# SCH_Naginata-left_2026-06-09.net
KiCad netlist of a schematic drawn in EasyEDA
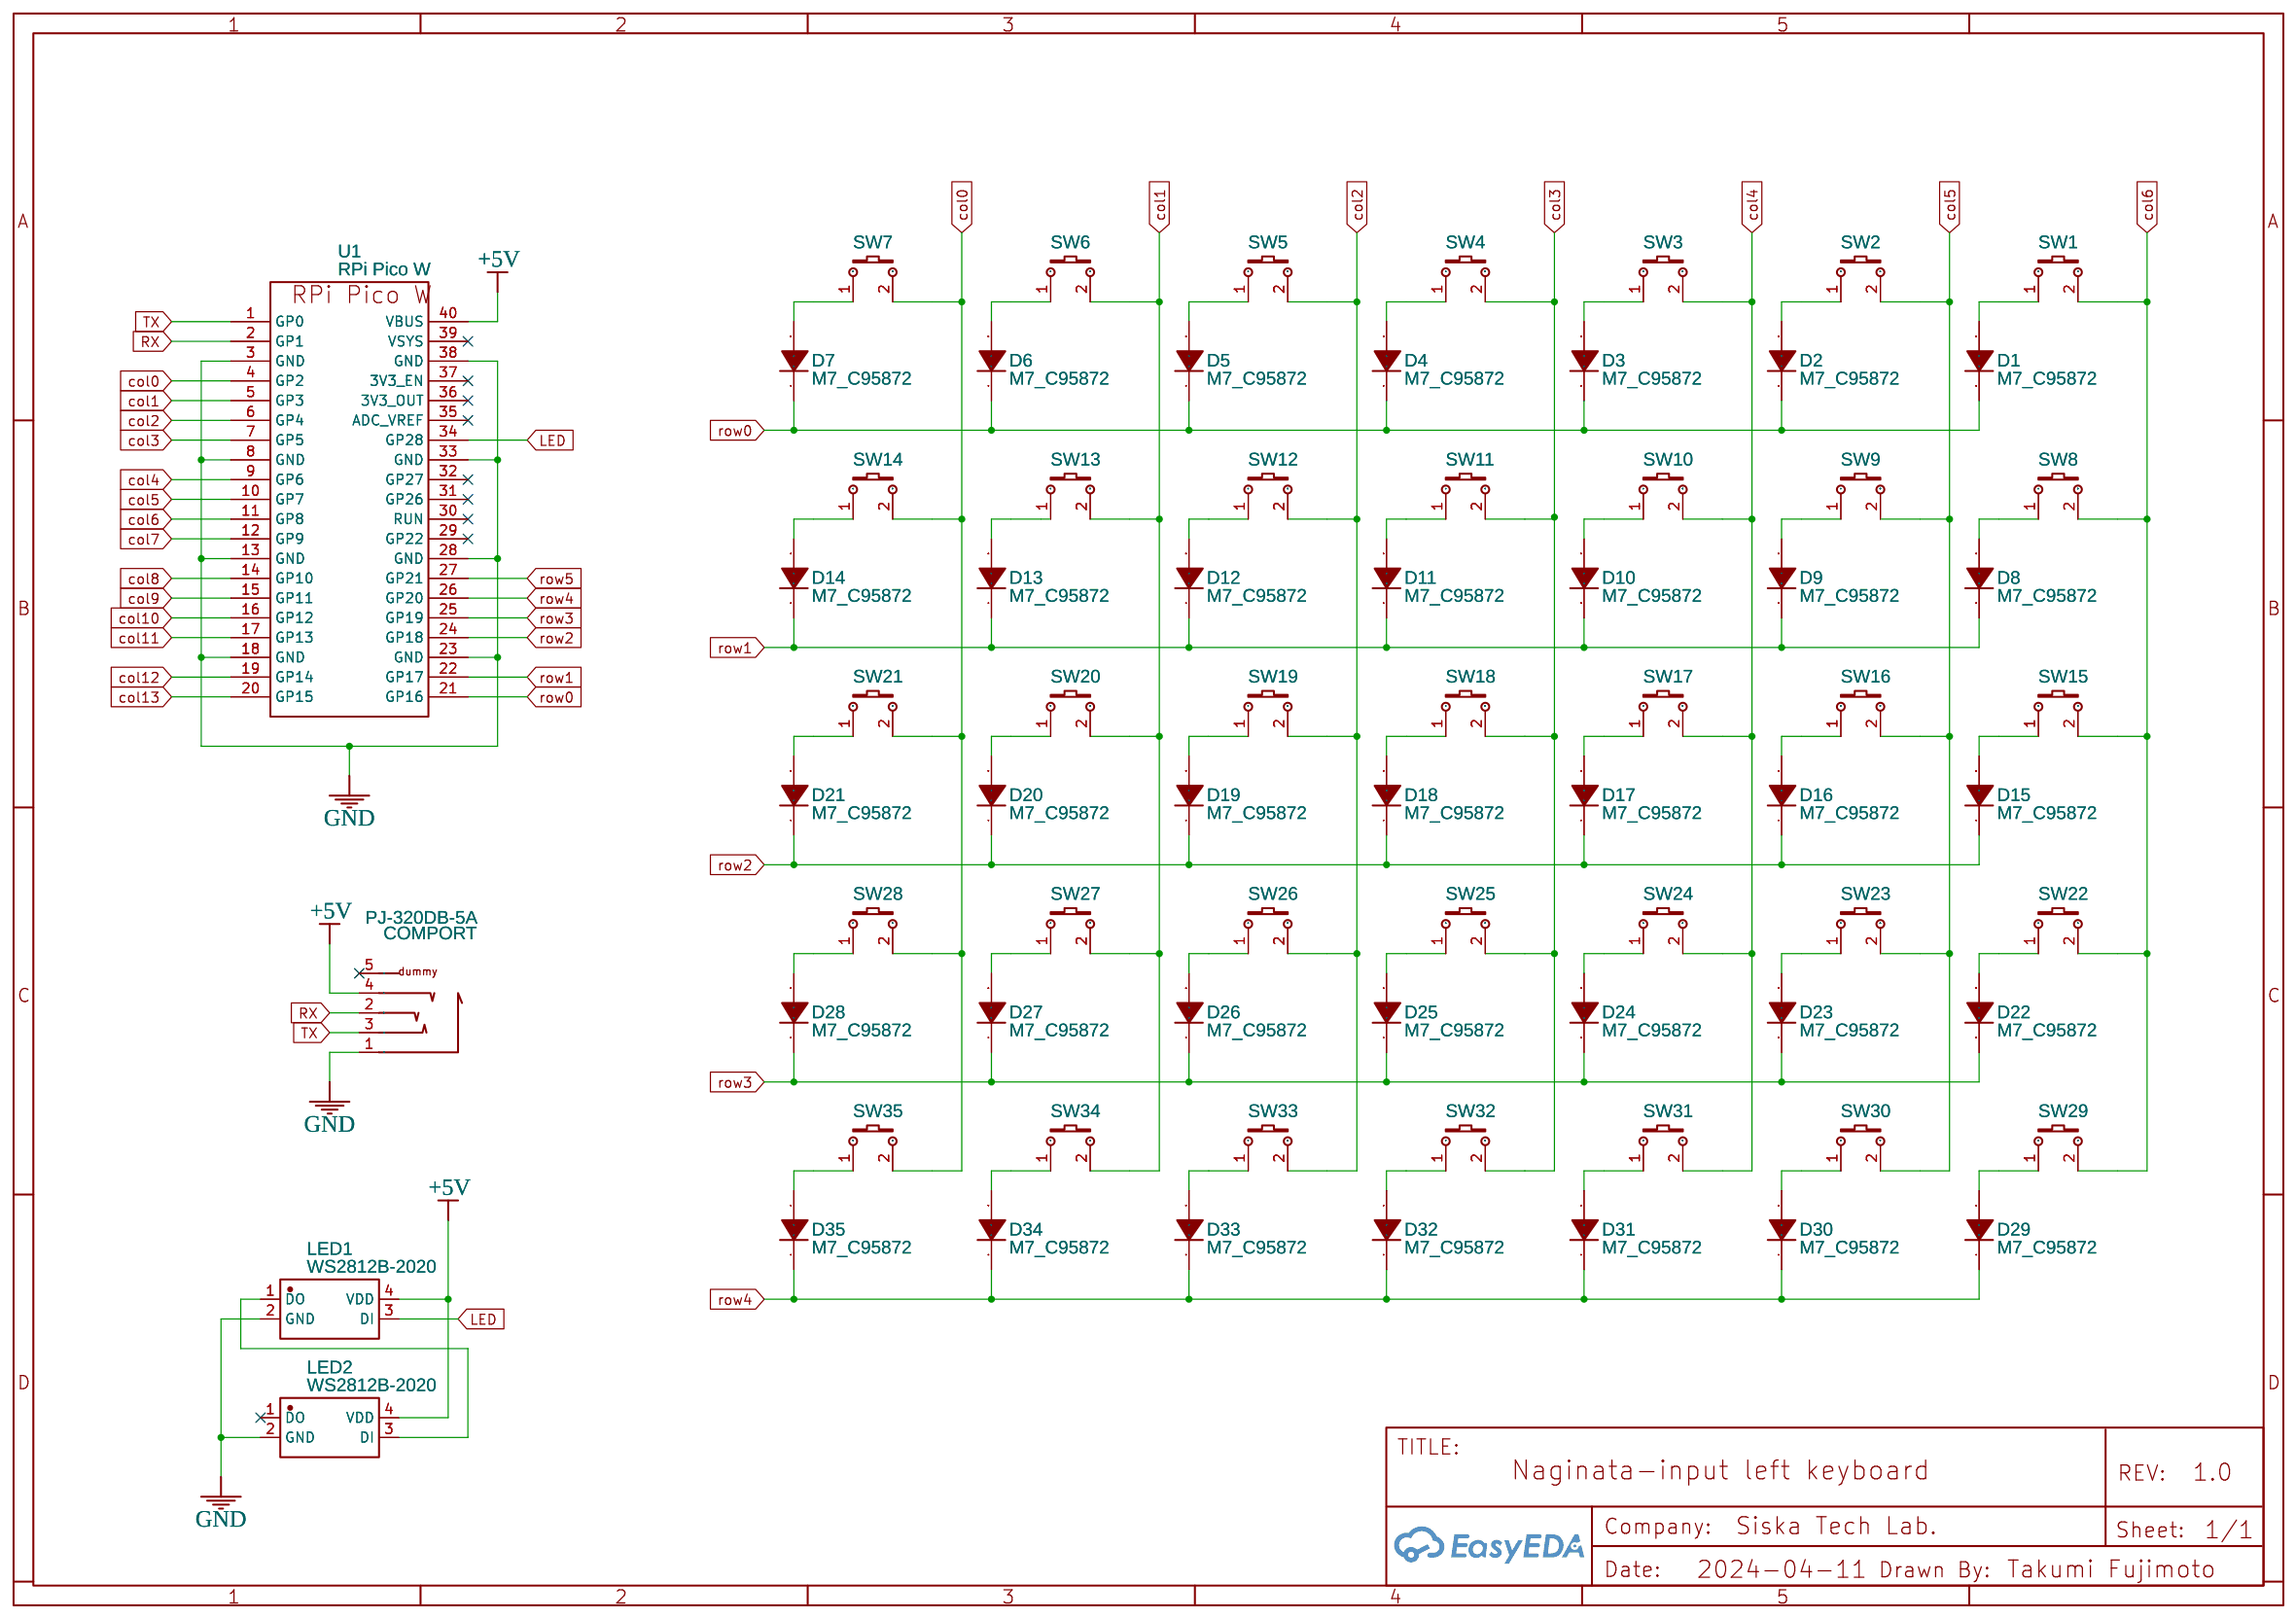
[diagram p0: schematic sheet]

(export (version "E")
  (design (tool "Eeschema 10.0.6"))
  (components
    (comp (ref "COMPORT")
      (value "PJ-320DB-5A")
      (fields (field (name "Manufacturer") "韩国韩荣"))
      (libsource (lib "") (part "PJ-320DB-5A"))
    )
    (comp (ref "D1")
      (value "M7_C95872")
      (fields (field (name "Manufacturer Part") "M7") (field (name "Manufacturer") "MDD"))
      (libsource (lib "") (part "M7_C95872"))
    )
    (comp (ref "D2")
      (value "M7_C95872")
      (fields (field (name "Manufacturer Part") "M7") (field (name "Manufacturer") "MDD"))
      (libsource (lib "") (part "M7_C95872"))
    )
    (comp (ref "D3")
      (value "M7_C95872")
      (fields (field (name "Manufacturer Part") "M7") (field (name "Manufacturer") "MDD"))
      (libsource (lib "") (part "M7_C95872"))
    )
    (comp (ref "D4")
      (value "M7_C95872")
      (fields (field (name "Manufacturer Part") "M7") (field (name "Manufacturer") "MDD"))
      (libsource (lib "") (part "M7_C95872"))
    )
    (comp (ref "D5")
      (value "M7_C95872")
      (fields (field (name "Manufacturer Part") "M7") (field (name "Manufacturer") "MDD"))
      (libsource (lib "") (part "M7_C95872"))
    )
    (comp (ref "D6")
      (value "M7_C95872")
      (fields (field (name "Manufacturer Part") "M7") (field (name "Manufacturer") "MDD"))
      (libsource (lib "") (part "M7_C95872"))
    )
    (comp (ref "D7")
      (value "M7_C95872")
      (fields (field (name "Manufacturer Part") "M7") (field (name "Manufacturer") "MDD"))
      (libsource (lib "") (part "M7_C95872"))
    )
    (comp (ref "D8")
      (value "M7_C95872")
      (fields (field (name "Manufacturer Part") "M7") (field (name "Manufacturer") "MDD"))
      (libsource (lib "") (part "M7_C95872"))
    )
    (comp (ref "D9")
      (value "M7_C95872")
      (fields (field (name "Manufacturer Part") "M7") (field (name "Manufacturer") "MDD"))
      (libsource (lib "") (part "M7_C95872"))
    )
    (comp (ref "D10")
      (value "M7_C95872")
      (fields (field (name "Manufacturer Part") "M7") (field (name "Manufacturer") "MDD"))
      (libsource (lib "") (part "M7_C95872"))
    )
    (comp (ref "D11")
      (value "M7_C95872")
      (fields (field (name "Manufacturer Part") "M7") (field (name "Manufacturer") "MDD"))
      (libsource (lib "") (part "M7_C95872"))
    )
    (comp (ref "D12")
      (value "M7_C95872")
      (fields (field (name "Manufacturer Part") "M7") (field (name "Manufacturer") "MDD"))
      (libsource (lib "") (part "M7_C95872"))
    )
    (comp (ref "D13")
      (value "M7_C95872")
      (fields (field (name "Manufacturer Part") "M7") (field (name "Manufacturer") "MDD"))
      (libsource (lib "") (part "M7_C95872"))
    )
    (comp (ref "D14")
      (value "M7_C95872")
      (fields (field (name "Manufacturer Part") "M7") (field (name "Manufacturer") "MDD"))
      (libsource (lib "") (part "M7_C95872"))
    )
    (comp (ref "D15")
      (value "M7_C95872")
      (fields (field (name "Manufacturer Part") "M7") (field (name "Manufacturer") "MDD"))
      (libsource (lib "") (part "M7_C95872"))
    )
    (comp (ref "D16")
      (value "M7_C95872")
      (fields (field (name "Manufacturer Part") "M7") (field (name "Manufacturer") "MDD"))
      (libsource (lib "") (part "M7_C95872"))
    )
    (comp (ref "D17")
      (value "M7_C95872")
      (fields (field (name "Manufacturer Part") "M7") (field (name "Manufacturer") "MDD"))
      (libsource (lib "") (part "M7_C95872"))
    )
    (comp (ref "D18")
      (value "M7_C95872")
      (fields (field (name "Manufacturer Part") "M7") (field (name "Manufacturer") "MDD"))
      (libsource (lib "") (part "M7_C95872"))
    )
    (comp (ref "D19")
      (value "M7_C95872")
      (fields (field (name "Manufacturer Part") "M7") (field (name "Manufacturer") "MDD"))
      (libsource (lib "") (part "M7_C95872"))
    )
    (comp (ref "D20")
      (value "M7_C95872")
      (fields (field (name "Manufacturer Part") "M7") (field (name "Manufacturer") "MDD"))
      (libsource (lib "") (part "M7_C95872"))
    )
    (comp (ref "D21")
      (value "M7_C95872")
      (fields (field (name "Manufacturer Part") "M7") (field (name "Manufacturer") "MDD"))
      (libsource (lib "") (part "M7_C95872"))
    )
    (comp (ref "D22")
      (value "M7_C95872")
      (fields (field (name "Manufacturer Part") "M7") (field (name "Manufacturer") "MDD"))
      (libsource (lib "") (part "M7_C95872"))
    )
    (comp (ref "D23")
      (value "M7_C95872")
      (fields (field (name "Manufacturer Part") "M7") (field (name "Manufacturer") "MDD"))
      (libsource (lib "") (part "M7_C95872"))
    )
    (comp (ref "D24")
      (value "M7_C95872")
      (fields (field (name "Manufacturer Part") "M7") (field (name "Manufacturer") "MDD"))
      (libsource (lib "") (part "M7_C95872"))
    )
    (comp (ref "D25")
      (value "M7_C95872")
      (fields (field (name "Manufacturer Part") "M7") (field (name "Manufacturer") "MDD"))
      (libsource (lib "") (part "M7_C95872"))
    )
    (comp (ref "D26")
      (value "M7_C95872")
      (fields (field (name "Manufacturer Part") "M7") (field (name "Manufacturer") "MDD"))
      (libsource (lib "") (part "M7_C95872"))
    )
    (comp (ref "D27")
      (value "M7_C95872")
      (fields (field (name "Manufacturer Part") "M7") (field (name "Manufacturer") "MDD"))
      (libsource (lib "") (part "M7_C95872"))
    )
    (comp (ref "D28")
      (value "M7_C95872")
      (fields (field (name "Manufacturer Part") "M7") (field (name "Manufacturer") "MDD"))
      (libsource (lib "") (part "M7_C95872"))
    )
    (comp (ref "D29")
      (value "M7_C95872")
      (fields (field (name "Manufacturer Part") "M7") (field (name "Manufacturer") "MDD"))
      (libsource (lib "") (part "M7_C95872"))
    )
    (comp (ref "D30")
      (value "M7_C95872")
      (fields (field (name "Manufacturer Part") "M7") (field (name "Manufacturer") "MDD"))
      (libsource (lib "") (part "M7_C95872"))
    )
    (comp (ref "D31")
      (value "M7_C95872")
      (fields (field (name "Manufacturer Part") "M7") (field (name "Manufacturer") "MDD"))
      (libsource (lib "") (part "M7_C95872"))
    )
    (comp (ref "D32")
      (value "M7_C95872")
      (fields (field (name "Manufacturer Part") "M7") (field (name "Manufacturer") "MDD"))
      (libsource (lib "") (part "M7_C95872"))
    )
    (comp (ref "D33")
      (value "M7_C95872")
      (fields (field (name "Manufacturer Part") "M7") (field (name "Manufacturer") "MDD"))
      (libsource (lib "") (part "M7_C95872"))
    )
    (comp (ref "D34")
      (value "M7_C95872")
      (fields (field (name "Manufacturer Part") "M7") (field (name "Manufacturer") "MDD"))
      (libsource (lib "") (part "M7_C95872"))
    )
    (comp (ref "D35")
      (value "M7_C95872")
      (fields (field (name "Manufacturer Part") "M7") (field (name "Manufacturer") "MDD"))
      (libsource (lib "") (part "M7_C95872"))
    )
    (comp (ref "LED1")
      (value "WS2812B-2020")
      (fields (field (name "Manufacturer") "worldsemi"))
      (libsource (lib "") (part "WS2812B-2020"))
    )
    (comp (ref "LED2")
      (value "WS2812B-2020")
      (fields (field (name "Manufacturer") "worldsemi"))
      (libsource (lib "") (part "WS2812B-2020"))
    )
    (comp (ref "SW1")
      (value "MX1A-11NW")
      (fields (field (name "Manufacturer") "CHERRY"))
      (libsource (lib "") (part "MX1A-11NW"))
    )
    (comp (ref "SW2")
      (value "MX1A-11NW")
      (fields (field (name "Manufacturer") "CHERRY"))
      (libsource (lib "") (part "MX1A-11NW"))
    )
    (comp (ref "SW3")
      (value "MX1A-11NW")
      (fields (field (name "Manufacturer") "CHERRY"))
      (libsource (lib "") (part "MX1A-11NW"))
    )
    (comp (ref "SW4")
      (value "MX1A-11NW")
      (fields (field (name "Manufacturer") "CHERRY"))
      (libsource (lib "") (part "MX1A-11NW"))
    )
    (comp (ref "SW5")
      (value "MX1A-11NW")
      (fields (field (name "Manufacturer") "CHERRY"))
      (libsource (lib "") (part "MX1A-11NW"))
    )
    (comp (ref "SW6")
      (value "MX1A-11NW")
      (fields (field (name "Manufacturer") "CHERRY"))
      (libsource (lib "") (part "MX1A-11NW"))
    )
    (comp (ref "SW7")
      (value "MX1A-11NW")
      (fields (field (name "Manufacturer") "CHERRY"))
      (libsource (lib "") (part "MX1A-11NW"))
    )
    (comp (ref "SW8")
      (value "MX1A-11NW")
      (fields (field (name "Manufacturer") "CHERRY"))
      (libsource (lib "") (part "MX1A-11NW"))
    )
    (comp (ref "SW9")
      (value "MX1A-11NW")
      (fields (field (name "Manufacturer") "CHERRY"))
      (libsource (lib "") (part "MX1A-11NW"))
    )
    (comp (ref "SW10")
      (value "MX1A-11NW")
      (fields (field (name "Manufacturer") "CHERRY"))
      (libsource (lib "") (part "MX1A-11NW"))
    )
    (comp (ref "SW11")
      (value "MX1A-11NW")
      (fields (field (name "Manufacturer") "CHERRY"))
      (libsource (lib "") (part "MX1A-11NW"))
    )
    (comp (ref "SW12")
      (value "MX1A-11NW")
      (fields (field (name "Manufacturer") "CHERRY"))
      (libsource (lib "") (part "MX1A-11NW"))
    )
    (comp (ref "SW13")
      (value "MX1A-11NW")
      (fields (field (name "Manufacturer") "CHERRY"))
      (libsource (lib "") (part "MX1A-11NW"))
    )
    (comp (ref "SW14")
      (value "MX1A-11NW")
      (fields (field (name "Manufacturer") "CHERRY"))
      (libsource (lib "") (part "MX1A-11NW"))
    )
    (comp (ref "SW15")
      (value "MX1A-11NW")
      (fields (field (name "Manufacturer") "CHERRY"))
      (libsource (lib "") (part "MX1A-11NW"))
    )
    (comp (ref "SW16")
      (value "MX1A-11NW")
      (fields (field (name "Manufacturer") "CHERRY"))
      (libsource (lib "") (part "MX1A-11NW"))
    )
    (comp (ref "SW17")
      (value "MX1A-11NW")
      (fields (field (name "Manufacturer") "CHERRY"))
      (libsource (lib "") (part "MX1A-11NW"))
    )
    (comp (ref "SW18")
      (value "MX1A-11NW")
      (fields (field (name "Manufacturer") "CHERRY"))
      (libsource (lib "") (part "MX1A-11NW"))
    )
    (comp (ref "SW19")
      (value "MX1A-11NW")
      (fields (field (name "Manufacturer") "CHERRY"))
      (libsource (lib "") (part "MX1A-11NW"))
    )
    (comp (ref "SW20")
      (value "MX1A-11NW")
      (fields (field (name "Manufacturer") "CHERRY"))
      (libsource (lib "") (part "MX1A-11NW"))
    )
    (comp (ref "SW21")
      (value "MX1A-11NW")
      (fields (field (name "Manufacturer") "CHERRY"))
      (libsource (lib "") (part "MX1A-11NW"))
    )
    (comp (ref "SW22")
      (value "MX1A-11NW")
      (fields (field (name "Manufacturer") "CHERRY"))
      (libsource (lib "") (part "MX1A-11NW"))
    )
    (comp (ref "SW23")
      (value "MX1A-11NW")
      (fields (field (name "Manufacturer") "CHERRY"))
      (libsource (lib "") (part "MX1A-11NW"))
    )
    (comp (ref "SW24")
      (value "MX1A-11NW")
      (fields (field (name "Manufacturer") "CHERRY"))
      (libsource (lib "") (part "MX1A-11NW"))
    )
    (comp (ref "SW25")
      (value "MX1A-11NW")
      (fields (field (name "Manufacturer") "CHERRY"))
      (libsource (lib "") (part "MX1A-11NW"))
    )
    (comp (ref "SW26")
      (value "MX1A-11NW")
      (fields (field (name "Manufacturer") "CHERRY"))
      (libsource (lib "") (part "MX1A-11NW"))
    )
    (comp (ref "SW27")
      (value "MX1A-11NW")
      (fields (field (name "Manufacturer") "CHERRY"))
      (libsource (lib "") (part "MX1A-11NW"))
    )
    (comp (ref "SW28")
      (value "MX1A-11NW")
      (fields (field (name "Manufacturer") "CHERRY"))
      (libsource (lib "") (part "MX1A-11NW"))
    )
    (comp (ref "SW29")
      (value "MX1A-11NW")
      (fields (field (name "Manufacturer") "CHERRY"))
      (libsource (lib "") (part "MX1A-11NW"))
    )
    (comp (ref "SW30")
      (value "MX1A-11NW")
      (fields (field (name "Manufacturer") "CHERRY"))
      (libsource (lib "") (part "MX1A-11NW"))
    )
    (comp (ref "SW31")
      (value "MX1A-11NW")
      (fields (field (name "Manufacturer") "CHERRY"))
      (libsource (lib "") (part "MX1A-11NW"))
    )
    (comp (ref "SW32")
      (value "MX1A-11NW")
      (fields (field (name "Manufacturer") "CHERRY"))
      (libsource (lib "") (part "MX1A-11NW"))
    )
    (comp (ref "SW33")
      (value "MX1A-11NW")
      (fields (field (name "Manufacturer") "CHERRY"))
      (libsource (lib "") (part "MX1A-11NW"))
    )
    (comp (ref "SW34")
      (value "MX1A-11NW")
      (fields (field (name "Manufacturer") "CHERRY"))
      (libsource (lib "") (part "MX1A-11NW"))
    )
    (comp (ref "SW35")
      (value "MX1A-11NW")
      (fields (field (name "Manufacturer") "CHERRY"))
      (libsource (lib "") (part "MX1A-11NW"))
    )
    (comp (ref "U1")
      (value "RPi Pico W")
      (fields
        (field (name "Manufacturer Part") "Pi Pico")
        (field (name "Manufacturer") "Raspberry Pi Foundation")
      )
      (libsource (lib "") (part "RPi Pico W"))
    )
  )
  (nets
    (net (code "1") (name "+5V") (class "Default")
      (node (ref "COMPORT") (pin "4") (pinfunction "4_4") (pintype "unspecified"))
      (node (ref "LED1") (pin "4") (pinfunction "VDD_4") (pintype "unspecified"))
      (node (ref "LED2") (pin "4") (pinfunction "VDD_4") (pintype "unspecified"))
      (node (ref "U1") (pin "40") (pinfunction "VBUS_40") (pintype "unspecified"))
    )
    (net (code "2") (name "GND") (class "Default")
      (node (ref "COMPORT") (pin "1") (pinfunction "1_1") (pintype "unspecified"))
      (node (ref "LED1") (pin "2") (pinfunction "GND_2") (pintype "unspecified"))
      (node (ref "LED2") (pin "2") (pinfunction "GND_2") (pintype "unspecified"))
      (node (ref "U1") (pin "13") (pinfunction "GND_13") (pintype "unspecified"))
      (node (ref "U1") (pin "18") (pinfunction "GND_18") (pintype "unspecified"))
      (node (ref "U1") (pin "23") (pinfunction "GND_23") (pintype "unspecified"))
      (node (ref "U1") (pin "28") (pinfunction "GND_28") (pintype "unspecified"))
      (node (ref "U1") (pin "3") (pinfunction "GND_3") (pintype "unspecified"))
      (node (ref "U1") (pin "33") (pinfunction "GND_33") (pintype "unspecified"))
      (node (ref "U1") (pin "38") (pinfunction "GND_38") (pintype "unspecified"))
      (node (ref "U1") (pin "8") (pinfunction "GND_8") (pintype "unspecified"))
    )
    (net (code "3") (name "LED") (class "Default")
      (node (ref "LED1") (pin "3") (pinfunction "DI_3") (pintype "unspecified"))
      (node (ref "U1") (pin "34") (pinfunction "GP28_34") (pintype "unspecified"))
    )
    (net (code "4") (name "Net-(D1-A)") (class "Default")
      (node (ref "D1") (pin "2") (pinfunction "A_2") (pintype "unspecified"))
      (node (ref "SW1") (pin "1") (pinfunction "1_1") (pintype "unspecified"))
    )
    (net (code "5") (name "Net-(D2-A)") (class "Default")
      (node (ref "D2") (pin "2") (pinfunction "A_2") (pintype "unspecified"))
      (node (ref "SW2") (pin "1") (pinfunction "1_1") (pintype "unspecified"))
    )
    (net (code "6") (name "Net-(D3-A)") (class "Default")
      (node (ref "D3") (pin "2") (pinfunction "A_2") (pintype "unspecified"))
      (node (ref "SW3") (pin "1") (pinfunction "1_1") (pintype "unspecified"))
    )
    (net (code "7") (name "Net-(D4-A)") (class "Default")
      (node (ref "D4") (pin "2") (pinfunction "A_2") (pintype "unspecified"))
      (node (ref "SW4") (pin "1") (pinfunction "1_1") (pintype "unspecified"))
    )
    (net (code "8") (name "Net-(D5-A)") (class "Default")
      (node (ref "D5") (pin "2") (pinfunction "A_2") (pintype "unspecified"))
      (node (ref "SW5") (pin "1") (pinfunction "1_1") (pintype "unspecified"))
    )
    (net (code "9") (name "Net-(D6-A)") (class "Default")
      (node (ref "D6") (pin "2") (pinfunction "A_2") (pintype "unspecified"))
      (node (ref "SW6") (pin "1") (pinfunction "1_1") (pintype "unspecified"))
    )
    (net (code "10") (name "Net-(D7-A)") (class "Default")
      (node (ref "D7") (pin "2") (pinfunction "A_2") (pintype "unspecified"))
      (node (ref "SW7") (pin "1") (pinfunction "1_1") (pintype "unspecified"))
    )
    (net (code "11") (name "Net-(D8-A)") (class "Default")
      (node (ref "D8") (pin "2") (pinfunction "A_2") (pintype "unspecified"))
      (node (ref "SW8") (pin "1") (pinfunction "1_1") (pintype "unspecified"))
    )
    (net (code "12") (name "Net-(D9-A)") (class "Default")
      (node (ref "D9") (pin "2") (pinfunction "A_2") (pintype "unspecified"))
      (node (ref "SW9") (pin "1") (pinfunction "1_1") (pintype "unspecified"))
    )
    (net (code "13") (name "Net-(D10-A)") (class "Default")
      (node (ref "D10") (pin "2") (pinfunction "A_2") (pintype "unspecified"))
      (node (ref "SW10") (pin "1") (pinfunction "1_1") (pintype "unspecified"))
    )
    (net (code "14") (name "Net-(D11-A)") (class "Default")
      (node (ref "D11") (pin "2") (pinfunction "A_2") (pintype "unspecified"))
      (node (ref "SW11") (pin "1") (pinfunction "1_1") (pintype "unspecified"))
    )
    (net (code "15") (name "Net-(D12-A)") (class "Default")
      (node (ref "D12") (pin "2") (pinfunction "A_2") (pintype "unspecified"))
      (node (ref "SW12") (pin "1") (pinfunction "1_1") (pintype "unspecified"))
    )
    (net (code "16") (name "Net-(D13-A)") (class "Default")
      (node (ref "D13") (pin "2") (pinfunction "A_2") (pintype "unspecified"))
      (node (ref "SW13") (pin "1") (pinfunction "1_1") (pintype "unspecified"))
    )
    (net (code "17") (name "Net-(D14-A)") (class "Default")
      (node (ref "D14") (pin "2") (pinfunction "A_2") (pintype "unspecified"))
      (node (ref "SW14") (pin "1") (pinfunction "1_1") (pintype "unspecified"))
    )
    (net (code "18") (name "Net-(D15-A)") (class "Default")
      (node (ref "D15") (pin "2") (pinfunction "A_2") (pintype "unspecified"))
      (node (ref "SW15") (pin "1") (pinfunction "1_1") (pintype "unspecified"))
    )
    (net (code "19") (name "Net-(D16-A)") (class "Default")
      (node (ref "D16") (pin "2") (pinfunction "A_2") (pintype "unspecified"))
      (node (ref "SW16") (pin "1") (pinfunction "1_1") (pintype "unspecified"))
    )
    (net (code "20") (name "Net-(D17-A)") (class "Default")
      (node (ref "D17") (pin "2") (pinfunction "A_2") (pintype "unspecified"))
      (node (ref "SW17") (pin "1") (pinfunction "1_1") (pintype "unspecified"))
    )
    (net (code "21") (name "Net-(D18-A)") (class "Default")
      (node (ref "D18") (pin "2") (pinfunction "A_2") (pintype "unspecified"))
      (node (ref "SW18") (pin "1") (pinfunction "1_1") (pintype "unspecified"))
    )
    (net (code "22") (name "Net-(D19-A)") (class "Default")
      (node (ref "D19") (pin "2") (pinfunction "A_2") (pintype "unspecified"))
      (node (ref "SW19") (pin "1") (pinfunction "1_1") (pintype "unspecified"))
    )
    (net (code "23") (name "Net-(D20-A)") (class "Default")
      (node (ref "D20") (pin "2") (pinfunction "A_2") (pintype "unspecified"))
      (node (ref "SW20") (pin "1") (pinfunction "1_1") (pintype "unspecified"))
    )
    (net (code "24") (name "Net-(D21-A)") (class "Default")
      (node (ref "D21") (pin "2") (pinfunction "A_2") (pintype "unspecified"))
      (node (ref "SW21") (pin "1") (pinfunction "1_1") (pintype "unspecified"))
    )
    (net (code "25") (name "Net-(D22-A)") (class "Default")
      (node (ref "D22") (pin "2") (pinfunction "A_2") (pintype "unspecified"))
      (node (ref "SW22") (pin "1") (pinfunction "1_1") (pintype "unspecified"))
    )
    (net (code "26") (name "Net-(D23-A)") (class "Default")
      (node (ref "D23") (pin "2") (pinfunction "A_2") (pintype "unspecified"))
      (node (ref "SW23") (pin "1") (pinfunction "1_1") (pintype "unspecified"))
    )
    (net (code "27") (name "Net-(D24-A)") (class "Default")
      (node (ref "D24") (pin "2") (pinfunction "A_2") (pintype "unspecified"))
      (node (ref "SW24") (pin "1") (pinfunction "1_1") (pintype "unspecified"))
    )
    (net (code "28") (name "Net-(D25-A)") (class "Default")
      (node (ref "D25") (pin "2") (pinfunction "A_2") (pintype "unspecified"))
      (node (ref "SW25") (pin "1") (pinfunction "1_1") (pintype "unspecified"))
    )
    (net (code "29") (name "Net-(D26-A)") (class "Default")
      (node (ref "D26") (pin "2") (pinfunction "A_2") (pintype "unspecified"))
      (node (ref "SW26") (pin "1") (pinfunction "1_1") (pintype "unspecified"))
    )
    (net (code "30") (name "Net-(D27-A)") (class "Default")
      (node (ref "D27") (pin "2") (pinfunction "A_2") (pintype "unspecified"))
      (node (ref "SW27") (pin "1") (pinfunction "1_1") (pintype "unspecified"))
    )
    (net (code "31") (name "Net-(D28-A)") (class "Default")
      (node (ref "D28") (pin "2") (pinfunction "A_2") (pintype "unspecified"))
      (node (ref "SW28") (pin "1") (pinfunction "1_1") (pintype "unspecified"))
    )
    (net (code "32") (name "Net-(D29-A)") (class "Default")
      (node (ref "D29") (pin "2") (pinfunction "A_2") (pintype "unspecified"))
      (node (ref "SW29") (pin "1") (pinfunction "1_1") (pintype "unspecified"))
    )
    (net (code "33") (name "Net-(D30-A)") (class "Default")
      (node (ref "D30") (pin "2") (pinfunction "A_2") (pintype "unspecified"))
      (node (ref "SW30") (pin "1") (pinfunction "1_1") (pintype "unspecified"))
    )
    (net (code "34") (name "Net-(D31-A)") (class "Default")
      (node (ref "D31") (pin "2") (pinfunction "A_2") (pintype "unspecified"))
      (node (ref "SW31") (pin "1") (pinfunction "1_1") (pintype "unspecified"))
    )
    (net (code "35") (name "Net-(D32-A)") (class "Default")
      (node (ref "D32") (pin "2") (pinfunction "A_2") (pintype "unspecified"))
      (node (ref "SW32") (pin "1") (pinfunction "1_1") (pintype "unspecified"))
    )
    (net (code "36") (name "Net-(D33-A)") (class "Default")
      (node (ref "D33") (pin "2") (pinfunction "A_2") (pintype "unspecified"))
      (node (ref "SW33") (pin "1") (pinfunction "1_1") (pintype "unspecified"))
    )
    (net (code "37") (name "Net-(D34-A)") (class "Default")
      (node (ref "D34") (pin "2") (pinfunction "A_2") (pintype "unspecified"))
      (node (ref "SW34") (pin "1") (pinfunction "1_1") (pintype "unspecified"))
    )
    (net (code "38") (name "Net-(D35-A)") (class "Default")
      (node (ref "D35") (pin "2") (pinfunction "A_2") (pintype "unspecified"))
      (node (ref "SW35") (pin "1") (pinfunction "1_1") (pintype "unspecified"))
    )
    (net (code "39") (name "Net-(LED1-DO)") (class "Default")
      (node (ref "LED1") (pin "1") (pinfunction "DO_1") (pintype "unspecified"))
      (node (ref "LED2") (pin "3") (pinfunction "DI_3") (pintype "unspecified"))
    )
    (net (code "40") (name "RX") (class "Default")
      (node (ref "COMPORT") (pin "2") (pinfunction "2_2") (pintype "unspecified"))
      (node (ref "U1") (pin "2") (pinfunction "GP1_2") (pintype "unspecified"))
    )
    (net (code "41") (name "TX") (class "Default")
      (node (ref "COMPORT") (pin "3") (pinfunction "3_3") (pintype "unspecified"))
      (node (ref "U1") (pin "1") (pinfunction "GP0_1") (pintype "unspecified"))
    )
    (net (code "42") (name "col0") (class "Default")
      (node (ref "SW14") (pin "2") (pinfunction "2_2") (pintype "unspecified"))
      (node (ref "SW21") (pin "2") (pinfunction "2_2") (pintype "unspecified"))
      (node (ref "SW28") (pin "2") (pinfunction "2_2") (pintype "unspecified"))
      (node (ref "SW35") (pin "2") (pinfunction "2_2") (pintype "unspecified"))
      (node (ref "SW7") (pin "2") (pinfunction "2_2") (pintype "unspecified"))
      (node (ref "U1") (pin "4") (pinfunction "GP2_4") (pintype "unspecified"))
    )
    (net (code "43") (name "col1") (class "Default")
      (node (ref "SW13") (pin "2") (pinfunction "2_2") (pintype "unspecified"))
      (node (ref "SW20") (pin "2") (pinfunction "2_2") (pintype "unspecified"))
      (node (ref "SW27") (pin "2") (pinfunction "2_2") (pintype "unspecified"))
      (node (ref "SW34") (pin "2") (pinfunction "2_2") (pintype "unspecified"))
      (node (ref "SW6") (pin "2") (pinfunction "2_2") (pintype "unspecified"))
      (node (ref "U1") (pin "5") (pinfunction "GP3_5") (pintype "unspecified"))
    )
    (net (code "44") (name "col2") (class "Default")
      (node (ref "SW12") (pin "2") (pinfunction "2_2") (pintype "unspecified"))
      (node (ref "SW19") (pin "2") (pinfunction "2_2") (pintype "unspecified"))
      (node (ref "SW26") (pin "2") (pinfunction "2_2") (pintype "unspecified"))
      (node (ref "SW33") (pin "2") (pinfunction "2_2") (pintype "unspecified"))
      (node (ref "SW5") (pin "2") (pinfunction "2_2") (pintype "unspecified"))
      (node (ref "U1") (pin "6") (pinfunction "GP4_6") (pintype "unspecified"))
    )
    (net (code "45") (name "col3") (class "Default")
      (node (ref "SW11") (pin "2") (pinfunction "2_2") (pintype "unspecified"))
      (node (ref "SW18") (pin "2") (pinfunction "2_2") (pintype "unspecified"))
      (node (ref "SW25") (pin "2") (pinfunction "2_2") (pintype "unspecified"))
      (node (ref "SW32") (pin "2") (pinfunction "2_2") (pintype "unspecified"))
      (node (ref "SW4") (pin "2") (pinfunction "2_2") (pintype "unspecified"))
      (node (ref "U1") (pin "7") (pinfunction "GP5_7") (pintype "unspecified"))
    )
    (net (code "46") (name "col4") (class "Default")
      (node (ref "SW10") (pin "2") (pinfunction "2_2") (pintype "unspecified"))
      (node (ref "SW17") (pin "2") (pinfunction "2_2") (pintype "unspecified"))
      (node (ref "SW24") (pin "2") (pinfunction "2_2") (pintype "unspecified"))
      (node (ref "SW3") (pin "2") (pinfunction "2_2") (pintype "unspecified"))
      (node (ref "SW31") (pin "2") (pinfunction "2_2") (pintype "unspecified"))
      (node (ref "U1") (pin "9") (pinfunction "GP6_9") (pintype "unspecified"))
    )
    (net (code "47") (name "col5") (class "Default")
      (node (ref "SW16") (pin "2") (pinfunction "2_2") (pintype "unspecified"))
      (node (ref "SW2") (pin "2") (pinfunction "2_2") (pintype "unspecified"))
      (node (ref "SW23") (pin "2") (pinfunction "2_2") (pintype "unspecified"))
      (node (ref "SW30") (pin "2") (pinfunction "2_2") (pintype "unspecified"))
      (node (ref "SW9") (pin "2") (pinfunction "2_2") (pintype "unspecified"))
      (node (ref "U1") (pin "10") (pinfunction "GP7_10") (pintype "unspecified"))
    )
    (net (code "48") (name "col6") (class "Default")
      (node (ref "SW1") (pin "2") (pinfunction "2_2") (pintype "unspecified"))
      (node (ref "SW15") (pin "2") (pinfunction "2_2") (pintype "unspecified"))
      (node (ref "SW22") (pin "2") (pinfunction "2_2") (pintype "unspecified"))
      (node (ref "SW29") (pin "2") (pinfunction "2_2") (pintype "unspecified"))
      (node (ref "SW8") (pin "2") (pinfunction "2_2") (pintype "unspecified"))
      (node (ref "U1") (pin "11") (pinfunction "GP8_11") (pintype "unspecified"))
    )
    (net (code "49") (name "col7") (class "Default")
      (node (ref "U1") (pin "12") (pinfunction "GP9_12") (pintype "unspecified"))
    )
    (net (code "50") (name "col8") (class "Default")
      (node (ref "U1") (pin "14") (pinfunction "GP10_14") (pintype "unspecified"))
    )
    (net (code "51") (name "col9") (class "Default")
      (node (ref "U1") (pin "15") (pinfunction "GP11_15") (pintype "unspecified"))
    )
    (net (code "52") (name "col10") (class "Default")
      (node (ref "U1") (pin "16") (pinfunction "GP12_16") (pintype "unspecified"))
    )
    (net (code "53") (name "col11") (class "Default")
      (node (ref "U1") (pin "17") (pinfunction "GP13_17") (pintype "unspecified"))
    )
    (net (code "54") (name "col12") (class "Default")
      (node (ref "U1") (pin "19") (pinfunction "GP14_19") (pintype "unspecified"))
    )
    (net (code "55") (name "col13") (class "Default")
      (node (ref "U1") (pin "20") (pinfunction "GP15_20") (pintype "unspecified"))
    )
    (net (code "56") (name "row0") (class "Default")
      (node (ref "D1") (pin "1") (pinfunction "K_1") (pintype "unspecified"))
      (node (ref "D2") (pin "1") (pinfunction "K_1") (pintype "unspecified"))
      (node (ref "D3") (pin "1") (pinfunction "K_1") (pintype "unspecified"))
      (node (ref "D4") (pin "1") (pinfunction "K_1") (pintype "unspecified"))
      (node (ref "D5") (pin "1") (pinfunction "K_1") (pintype "unspecified"))
      (node (ref "D6") (pin "1") (pinfunction "K_1") (pintype "unspecified"))
      (node (ref "D7") (pin "1") (pinfunction "K_1") (pintype "unspecified"))
      (node (ref "U1") (pin "21") (pinfunction "GP16_21") (pintype "unspecified"))
    )
    (net (code "57") (name "row1") (class "Default")
      (node (ref "D10") (pin "1") (pinfunction "K_1") (pintype "unspecified"))
      (node (ref "D11") (pin "1") (pinfunction "K_1") (pintype "unspecified"))
      (node (ref "D12") (pin "1") (pinfunction "K_1") (pintype "unspecified"))
      (node (ref "D13") (pin "1") (pinfunction "K_1") (pintype "unspecified"))
      (node (ref "D14") (pin "1") (pinfunction "K_1") (pintype "unspecified"))
      (node (ref "D8") (pin "1") (pinfunction "K_1") (pintype "unspecified"))
      (node (ref "D9") (pin "1") (pinfunction "K_1") (pintype "unspecified"))
      (node (ref "U1") (pin "22") (pinfunction "GP17_22") (pintype "unspecified"))
    )
    (net (code "58") (name "row2") (class "Default")
      (node (ref "D15") (pin "1") (pinfunction "K_1") (pintype "unspecified"))
      (node (ref "D16") (pin "1") (pinfunction "K_1") (pintype "unspecified"))
      (node (ref "D17") (pin "1") (pinfunction "K_1") (pintype "unspecified"))
      (node (ref "D18") (pin "1") (pinfunction "K_1") (pintype "unspecified"))
      (node (ref "D19") (pin "1") (pinfunction "K_1") (pintype "unspecified"))
      (node (ref "D20") (pin "1") (pinfunction "K_1") (pintype "unspecified"))
      (node (ref "D21") (pin "1") (pinfunction "K_1") (pintype "unspecified"))
      (node (ref "U1") (pin "24") (pinfunction "GP18_24") (pintype "unspecified"))
    )
    (net (code "59") (name "row3") (class "Default")
      (node (ref "D22") (pin "1") (pinfunction "K_1") (pintype "unspecified"))
      (node (ref "D23") (pin "1") (pinfunction "K_1") (pintype "unspecified"))
      (node (ref "D24") (pin "1") (pinfunction "K_1") (pintype "unspecified"))
      (node (ref "D25") (pin "1") (pinfunction "K_1") (pintype "unspecified"))
      (node (ref "D26") (pin "1") (pinfunction "K_1") (pintype "unspecified"))
      (node (ref "D27") (pin "1") (pinfunction "K_1") (pintype "unspecified"))
      (node (ref "D28") (pin "1") (pinfunction "K_1") (pintype "unspecified"))
      (node (ref "U1") (pin "25") (pinfunction "GP19_25") (pintype "unspecified"))
    )
    (net (code "60") (name "row4") (class "Default")
      (node (ref "D29") (pin "1") (pinfunction "K_1") (pintype "unspecified"))
      (node (ref "D30") (pin "1") (pinfunction "K_1") (pintype "unspecified"))
      (node (ref "D31") (pin "1") (pinfunction "K_1") (pintype "unspecified"))
      (node (ref "D32") (pin "1") (pinfunction "K_1") (pintype "unspecified"))
      (node (ref "D33") (pin "1") (pinfunction "K_1") (pintype "unspecified"))
      (node (ref "D34") (pin "1") (pinfunction "K_1") (pintype "unspecified"))
      (node (ref "D35") (pin "1") (pinfunction "K_1") (pintype "unspecified"))
      (node (ref "U1") (pin "26") (pinfunction "GP20_26") (pintype "unspecified"))
    )
    (net (code "61") (name "row5") (class "Default")
      (node (ref "U1") (pin "27") (pinfunction "GP21_27") (pintype "unspecified"))
    )
    (net (code "62") (name "unconnected-(COMPORT-Pad5)") (class "Default")
      (node (ref "COMPORT") (pin "5") (pinfunction "5_5") (pintype "unspecified+no_connect"))
    )
    (net (code "63") (name "unconnected-(LED2-DO-Pad1)") (class "Default")
      (node (ref "LED2") (pin "1") (pinfunction "DO_1") (pintype "unspecified+no_connect"))
    )
    (net (code "64") (name "unconnected-(U1-3V3_EN-Pad37)") (class "Default")
      (node (ref "U1") (pin "37") (pinfunction "3V3_EN_37") (pintype "unspecified+no_connect"))
    )
    (net (code "65") (name "unconnected-(U1-3V3_OUT-Pad36)") (class "Default")
      (node (ref "U1") (pin "36") (pinfunction "3V3_OUT_36") (pintype "unspecified+no_connect"))
    )
    (net (code "66") (name "unconnected-(U1-ADC_VREF-Pad35)") (class "Default")
      (node (ref "U1") (pin "35") (pinfunction "ADC_VREF_35") (pintype "unspecified+no_connect"))
    )
    (net (code "67") (name "unconnected-(U1-GP22-Pad29)") (class "Default")
      (node (ref "U1") (pin "29") (pinfunction "GP22_29") (pintype "unspecified+no_connect"))
    )
    (net (code "68") (name "unconnected-(U1-GP26-Pad31)") (class "Default")
      (node (ref "U1") (pin "31") (pinfunction "GP26_31") (pintype "unspecified+no_connect"))
    )
    (net (code "69") (name "unconnected-(U1-GP27-Pad32)") (class "Default")
      (node (ref "U1") (pin "32") (pinfunction "GP27_32") (pintype "unspecified+no_connect"))
    )
    (net (code "70") (name "unconnected-(U1-RUN-Pad30)") (class "Default")
      (node (ref "U1") (pin "30") (pinfunction "RUN_30") (pintype "unspecified+no_connect"))
    )
    (net (code "71") (name "unconnected-(U1-VSYS-Pad39)") (class "Default")
      (node (ref "U1") (pin "39") (pinfunction "VSYS_39") (pintype "unspecified+no_connect"))
    )
  )
)
